# Rear_brake_lamp.net
KiCad netlist of a schematic drawn in EAGLE
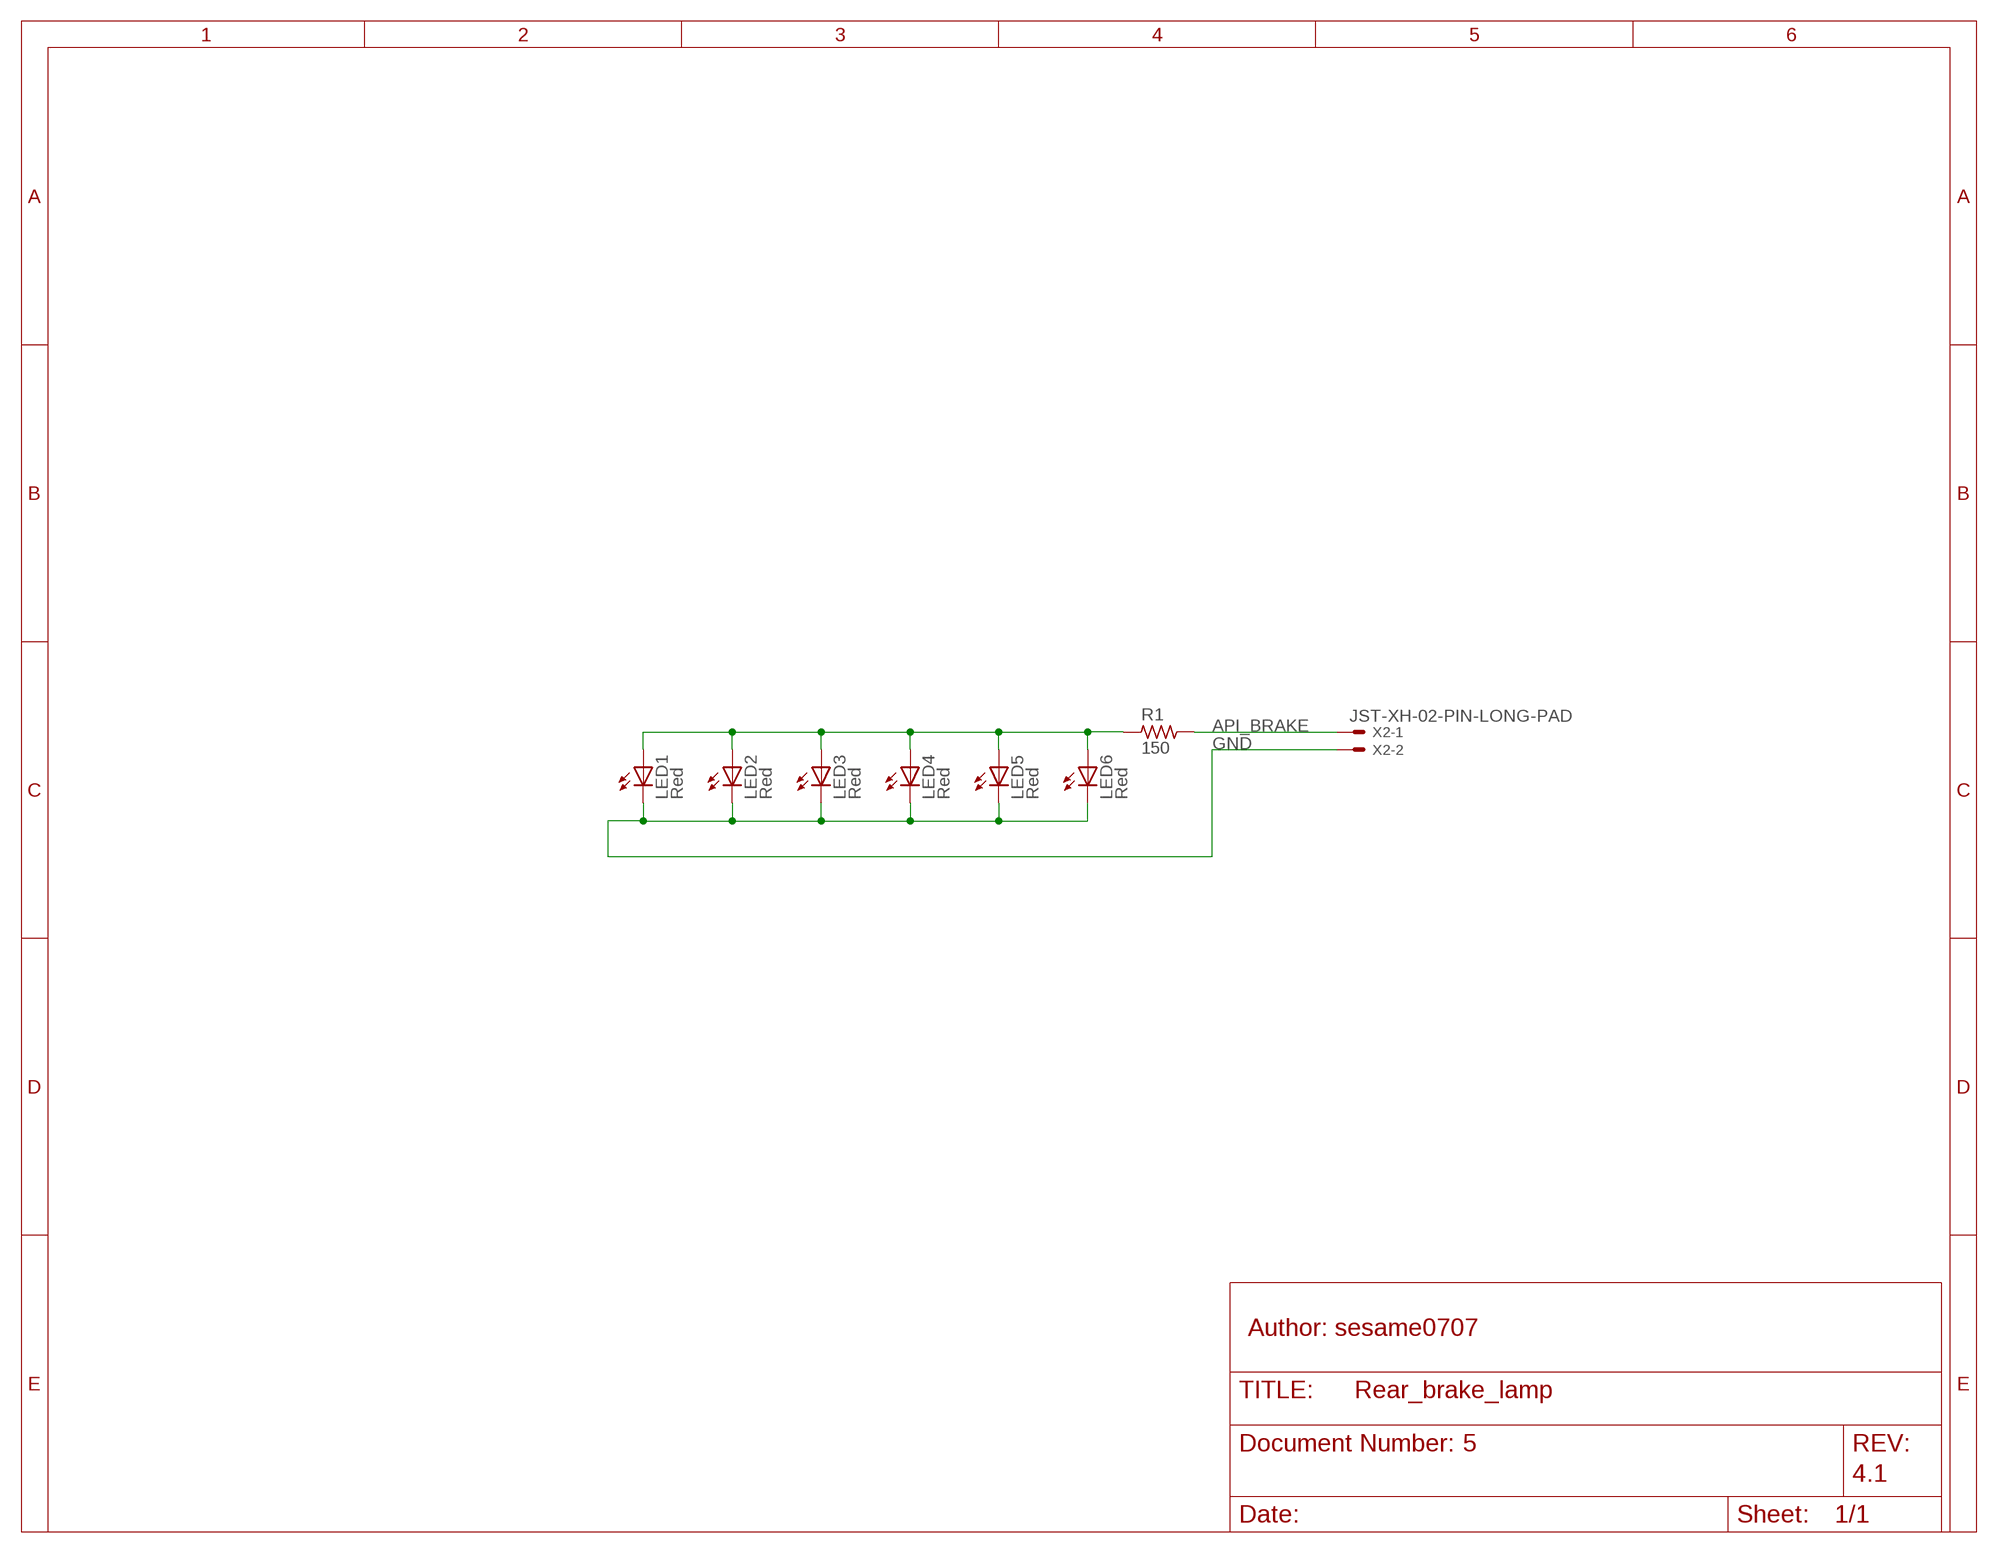
[diagram p0: schematic, sheet 1]

(export (version "E")
  (design (tool "Eeschema 10.0.6"))
  (components
    (comp (ref "LED1")
      (value "Red")
      (footprint "eagle-import:LED5MM")
      (fields
        (field (name "MANUFACTURER") "LUCKYLIGHT")
        (field (name "MANUFACTURER_PART_NUMBER") "LL-503VD2E-1B")
      )
      (libsource (lib "eagle-import") (part "LED5MM"))
    )
    (comp (ref "LED2")
      (value "Red")
      (footprint "eagle-import:LED5MM")
      (fields
        (field (name "MANUFACTURER") "LUCKYLIGHT")
        (field (name "MANUFACTURER_PART_NUMBER") "LL-503VD2E-1B")
      )
      (libsource (lib "eagle-import") (part "LED5MM"))
    )
    (comp (ref "LED3")
      (value "Red")
      (footprint "eagle-import:LED5MM")
      (fields
        (field (name "MANUFACTURER") "LUCKYLIGHT")
        (field (name "MANUFACTURER_PART_NUMBER") "LL-503VD2E-1B")
      )
      (libsource (lib "eagle-import") (part "LED5MM"))
    )
    (comp (ref "LED4")
      (value "Red")
      (footprint "eagle-import:LED5MM")
      (fields
        (field (name "MANUFACTURER") "LUCKYLIGHT")
        (field (name "MANUFACTURER_PART_NUMBER") "LL-503VD2E-1B")
      )
      (libsource (lib "eagle-import") (part "LED5MM"))
    )
    (comp (ref "LED5")
      (value "Red")
      (footprint "eagle-import:LED5MM")
      (fields
        (field (name "MANUFACTURER") "LUCKYLIGHT")
        (field (name "MANUFACTURER_PART_NUMBER") "LL-503VD2E-1B")
      )
      (libsource (lib "eagle-import") (part "LED5MM"))
    )
    (comp (ref "LED6")
      (value "Red")
      (footprint "eagle-import:LED5MM")
      (fields
        (field (name "MANUFACTURER") "LUCKYLIGHT")
        (field (name "MANUFACTURER_PART_NUMBER") "LL-503VD2E-1B")
      )
      (libsource (lib "eagle-import") (part "LED5MM"))
    )
    (comp (ref "R1")
      (value "150")
      (footprint "eagle-import:R1206")
      (fields
        (field (name "MANUFACTURER") "ROYAL OHM")
        (field (name "MANUFACTURER_PART_NUMBER") "1206S4J0151T5E")
      )
      (libsource (lib "eagle-import") (part "R_1206"))
    )
    (comp (ref "X2")
      (value "JST-XH-02-PIN-LONG-PAD")
      (footprint "eagle-import:JST-XH-02-PACKAGE-LONG-PAD")
      (libsource (lib "eagle-import") (part "JST-XH-02-PIN-LONG-PAD"))
    )
  )
  (nets
    (net (code "1") (name "/API_BRAKE") (class "Default")
      (node (ref "LED1") (pin "A") (pinfunction "A_A") (pintype "passive"))
      (node (ref "LED2") (pin "A") (pinfunction "A_A") (pintype "passive"))
      (node (ref "LED3") (pin "A") (pinfunction "A_A") (pintype "passive"))
      (node (ref "LED4") (pin "A") (pinfunction "A_A") (pintype "passive"))
      (node (ref "LED5") (pin "A") (pinfunction "A_A") (pintype "passive"))
      (node (ref "LED6") (pin "A") (pinfunction "A_A") (pintype "passive"))
      (node (ref "R1") (pin "1") (pinfunction "1_1") (pintype "passive"))
    )
    (net (code "2") (name "/GND") (class "Default")
      (node (ref "LED1") (pin "K") (pinfunction "C_K") (pintype "passive"))
      (node (ref "LED2") (pin "K") (pinfunction "C_K") (pintype "passive"))
      (node (ref "LED3") (pin "K") (pinfunction "C_K") (pintype "passive"))
      (node (ref "LED4") (pin "K") (pinfunction "C_K") (pintype "passive"))
      (node (ref "LED5") (pin "K") (pinfunction "C_K") (pintype "passive"))
      (node (ref "LED6") (pin "K") (pinfunction "C_K") (pintype "passive"))
      (node (ref "X2") (pin "2") (pinfunction "S_2") (pintype "passive"))
    )
    (net (code "3") (name "Net-(X2A-S)") (class "Default")
      (node (ref "R1") (pin "2") (pinfunction "2_2") (pintype "passive"))
      (node (ref "X2") (pin "1") (pinfunction "S_1") (pintype "passive"))
    )
  )
)
